# sch_cm4_ethernet.net
KiCad netlist of a schematic drawn in Altium Designer
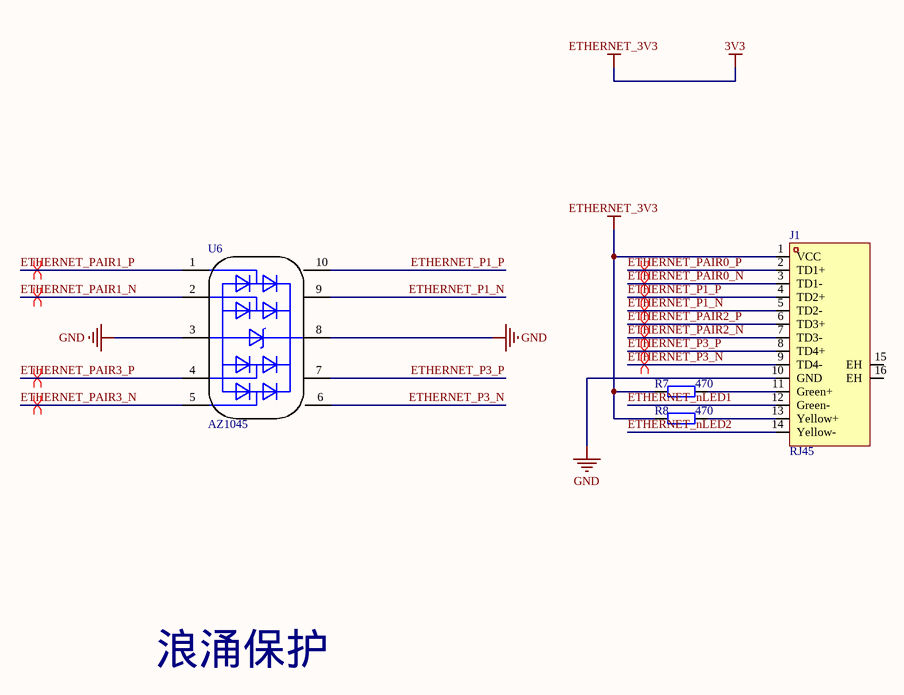
[diagram p0: sch_cm4_ethernet.SchDoc]

(export (version "E")
  (design (tool "Eeschema 10.0.6"))
  (components
    (comp (ref "J1") (value "RJ45") (footprint "RJ45") (libsource (lib "schlib_cm4") (part "RJ45")))
    (comp (ref "R7")
      (value "470")
      (footprint "R 0603_L")
      (description "贴片电阻")
      (fields (field (name "版权归属") "来自淘宝 ID：黄晶宝石"))
      (libsource (lib "0.1 - 电阻-电容-电感") (part "R"))
    )
    (comp (ref "R8")
      (value "470")
      (footprint "R 0603_L")
      (description "贴片电阻")
      (fields (field (name "版权归属") "来自淘宝 ID：黄晶宝石"))
      (libsource (lib "0.1 - 电阻-电容-电感") (part "R"))
    )
    (comp (ref "U6") (value "AZ1045") (footprint "AZ1045-04F") (libsource (lib "schlib_cm4") (part "AZ1045")))
  )
  (nets
    (net (code "1") (name "/ETHERNET_P1_N") (class "Default")
      (node (ref "J1") (pin "5") (pinfunction "TD2-_5") (pintype "passive"))
      (node (ref "U6") (pin "9") (pinfunction "NC_9") (pintype "passive"))
    )
    (net (code "2") (name "/ETHERNET_P1_P") (class "Default")
      (node (ref "J1") (pin "4") (pinfunction "TD2+_4") (pintype "passive"))
      (node (ref "U6") (pin "10") (pinfunction "NC_10") (pintype "passive"))
    )
    (net (code "3") (name "/ETHERNET_P3_N") (class "Default")
      (node (ref "J1") (pin "9") (pinfunction "TD4-_9") (pintype "passive"))
      (node (ref "U6") (pin "6") (pinfunction "NC_6") (pintype "passive"))
    )
    (net (code "4") (name "/ETHERNET_P3_P") (class "Default")
      (node (ref "J1") (pin "8") (pinfunction "TD4+_8") (pintype "passive"))
      (node (ref "U6") (pin "7") (pinfunction "NC_7") (pintype "passive"))
    )
    (net (code "5") (name "/ETHERNET_PAIR0_N") (class "Default")
      (node (ref "J1") (pin "3") (pinfunction "TD1-_3") (pintype "passive"))
    )
    (net (code "6") (name "/ETHERNET_PAIR0_P") (class "Default")
      (node (ref "J1") (pin "2") (pinfunction "TD1+_2") (pintype "passive"))
    )
    (net (code "7") (name "/ETHERNET_PAIR1_N") (class "Default")
      (node (ref "U6") (pin "2") (pinfunction "I/O_2_2") (pintype "passive"))
    )
    (net (code "8") (name "/ETHERNET_PAIR1_P") (class "Default")
      (node (ref "U6") (pin "1") (pinfunction "I/O_1_1") (pintype "passive"))
    )
    (net (code "9") (name "/ETHERNET_PAIR2_N") (class "Default")
      (node (ref "J1") (pin "7") (pinfunction "TD3-_7") (pintype "passive"))
    )
    (net (code "10") (name "/ETHERNET_PAIR2_P") (class "Default")
      (node (ref "J1") (pin "6") (pinfunction "TD3+_6") (pintype "passive"))
    )
    (net (code "11") (name "/ETHERNET_PAIR3_N") (class "Default")
      (node (ref "U6") (pin "5") (pinfunction "I/O_4_5") (pintype "passive"))
    )
    (net (code "12") (name "/ETHERNET_PAIR3_P") (class "Default")
      (node (ref "U6") (pin "4") (pinfunction "I/O_3_4") (pintype "passive"))
    )
    (net (code "13") (name "/ETHERNET_nLED1") (class "Default")
      (node (ref "J1") (pin "12") (pinfunction "Green-_12") (pintype "passive"))
    )
    (net (code "14") (name "/ETHERNET_nLED2") (class "Default")
      (node (ref "J1") (pin "14") (pinfunction "Yellow-_14") (pintype "passive"))
    )
    (net (code "15") (name "3V3") (class "Default")
      (node (ref "J1") (pin "1") (pinfunction "VCC_1") (pintype "passive"))
      (node (ref "R7") (pin "1") (pinfunction "1_1") (pintype "passive"))
      (node (ref "R8") (pin "1") (pinfunction "1_1") (pintype "passive"))
    )
    (net (code "16") (name "GND") (class "Default")
      (node (ref "J1") (pin "10") (pinfunction "GND_10") (pintype "passive"))
      (node (ref "U6") (pin "3") (pinfunction "GND_3") (pintype "passive"))
      (node (ref "U6") (pin "8") (pinfunction "GND_8") (pintype "passive"))
    )
    (net (code "17") (name "Net-(J1-Green+)") (class "Default")
      (node (ref "J1") (pin "11") (pinfunction "Green+_11") (pintype "passive"))
      (node (ref "R7") (pin "2") (pinfunction "2_2") (pintype "passive"))
    )
    (net (code "18") (name "Net-(J1-Yellow+)") (class "Default")
      (node (ref "J1") (pin "13") (pinfunction "Yellow+_13") (pintype "passive"))
      (node (ref "R8") (pin "2") (pinfunction "2_2") (pintype "passive"))
    )
    (net (code "19") (name "unconnected-(J1-EH-Pad15)") (class "Default")
      (node (ref "J1") (pin "15") (pinfunction "EH_15") (pintype "passive"))
    )
    (net (code "20") (name "unconnected-(J1-EH-Pad16)") (class "Default")
      (node (ref "J1") (pin "16") (pinfunction "EH_16") (pintype "passive"))
    )
  )
)
